# eink_controller.net
KiCad netlist of a schematic drawn in EAGLE
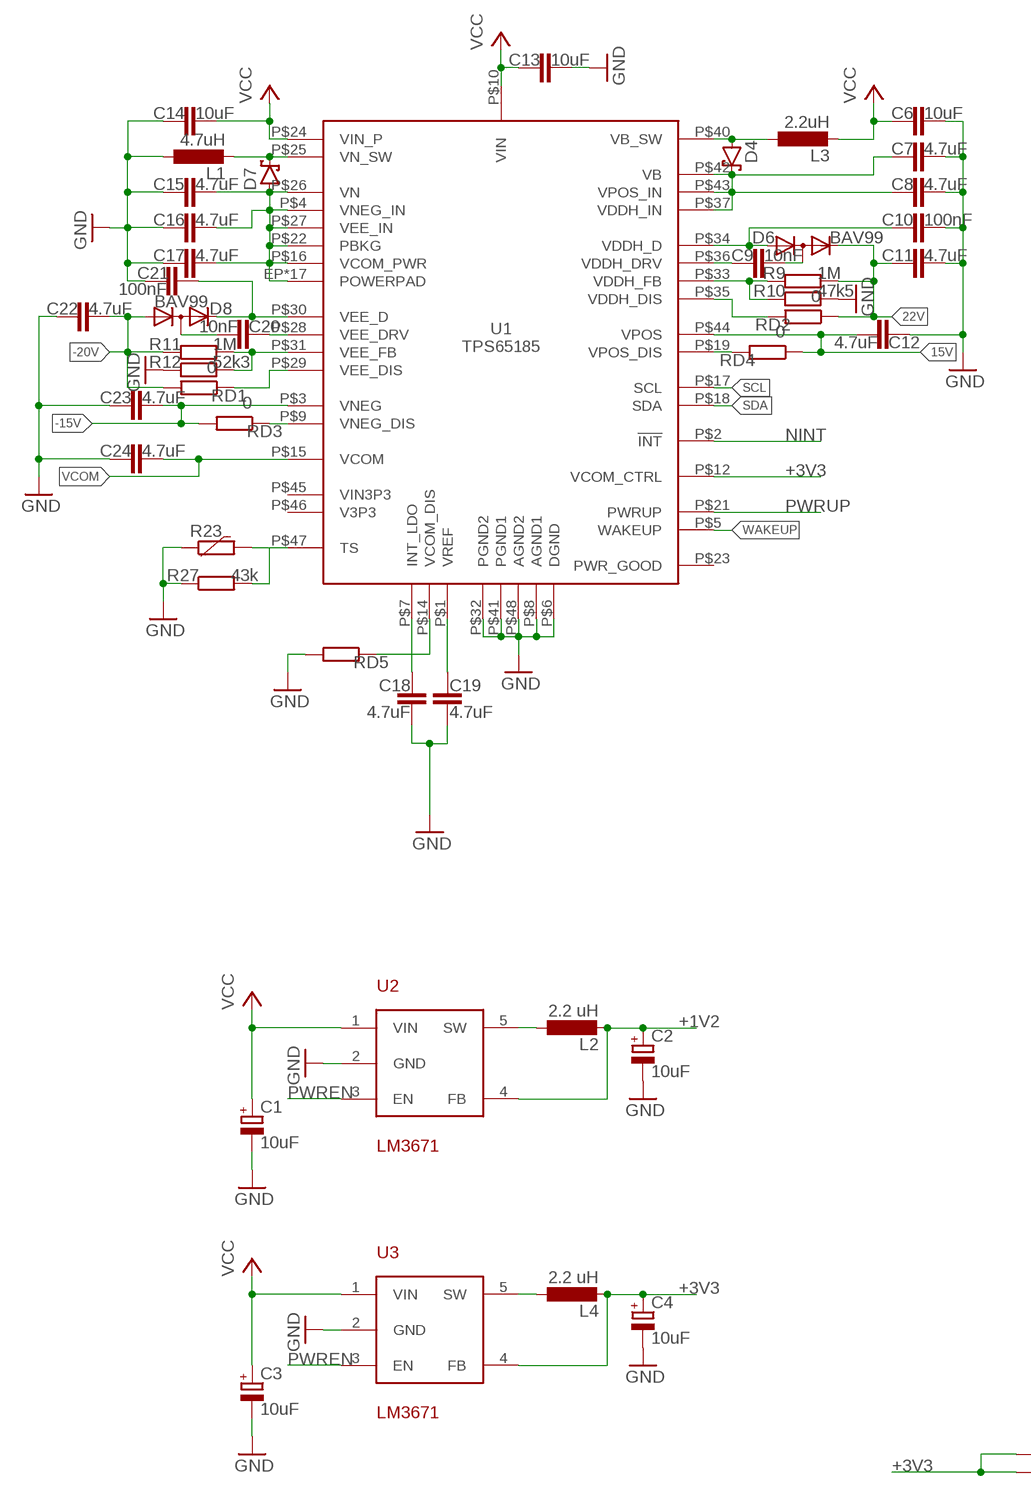
[diagram p0: schematic, sheet 1, part 1 of 2]
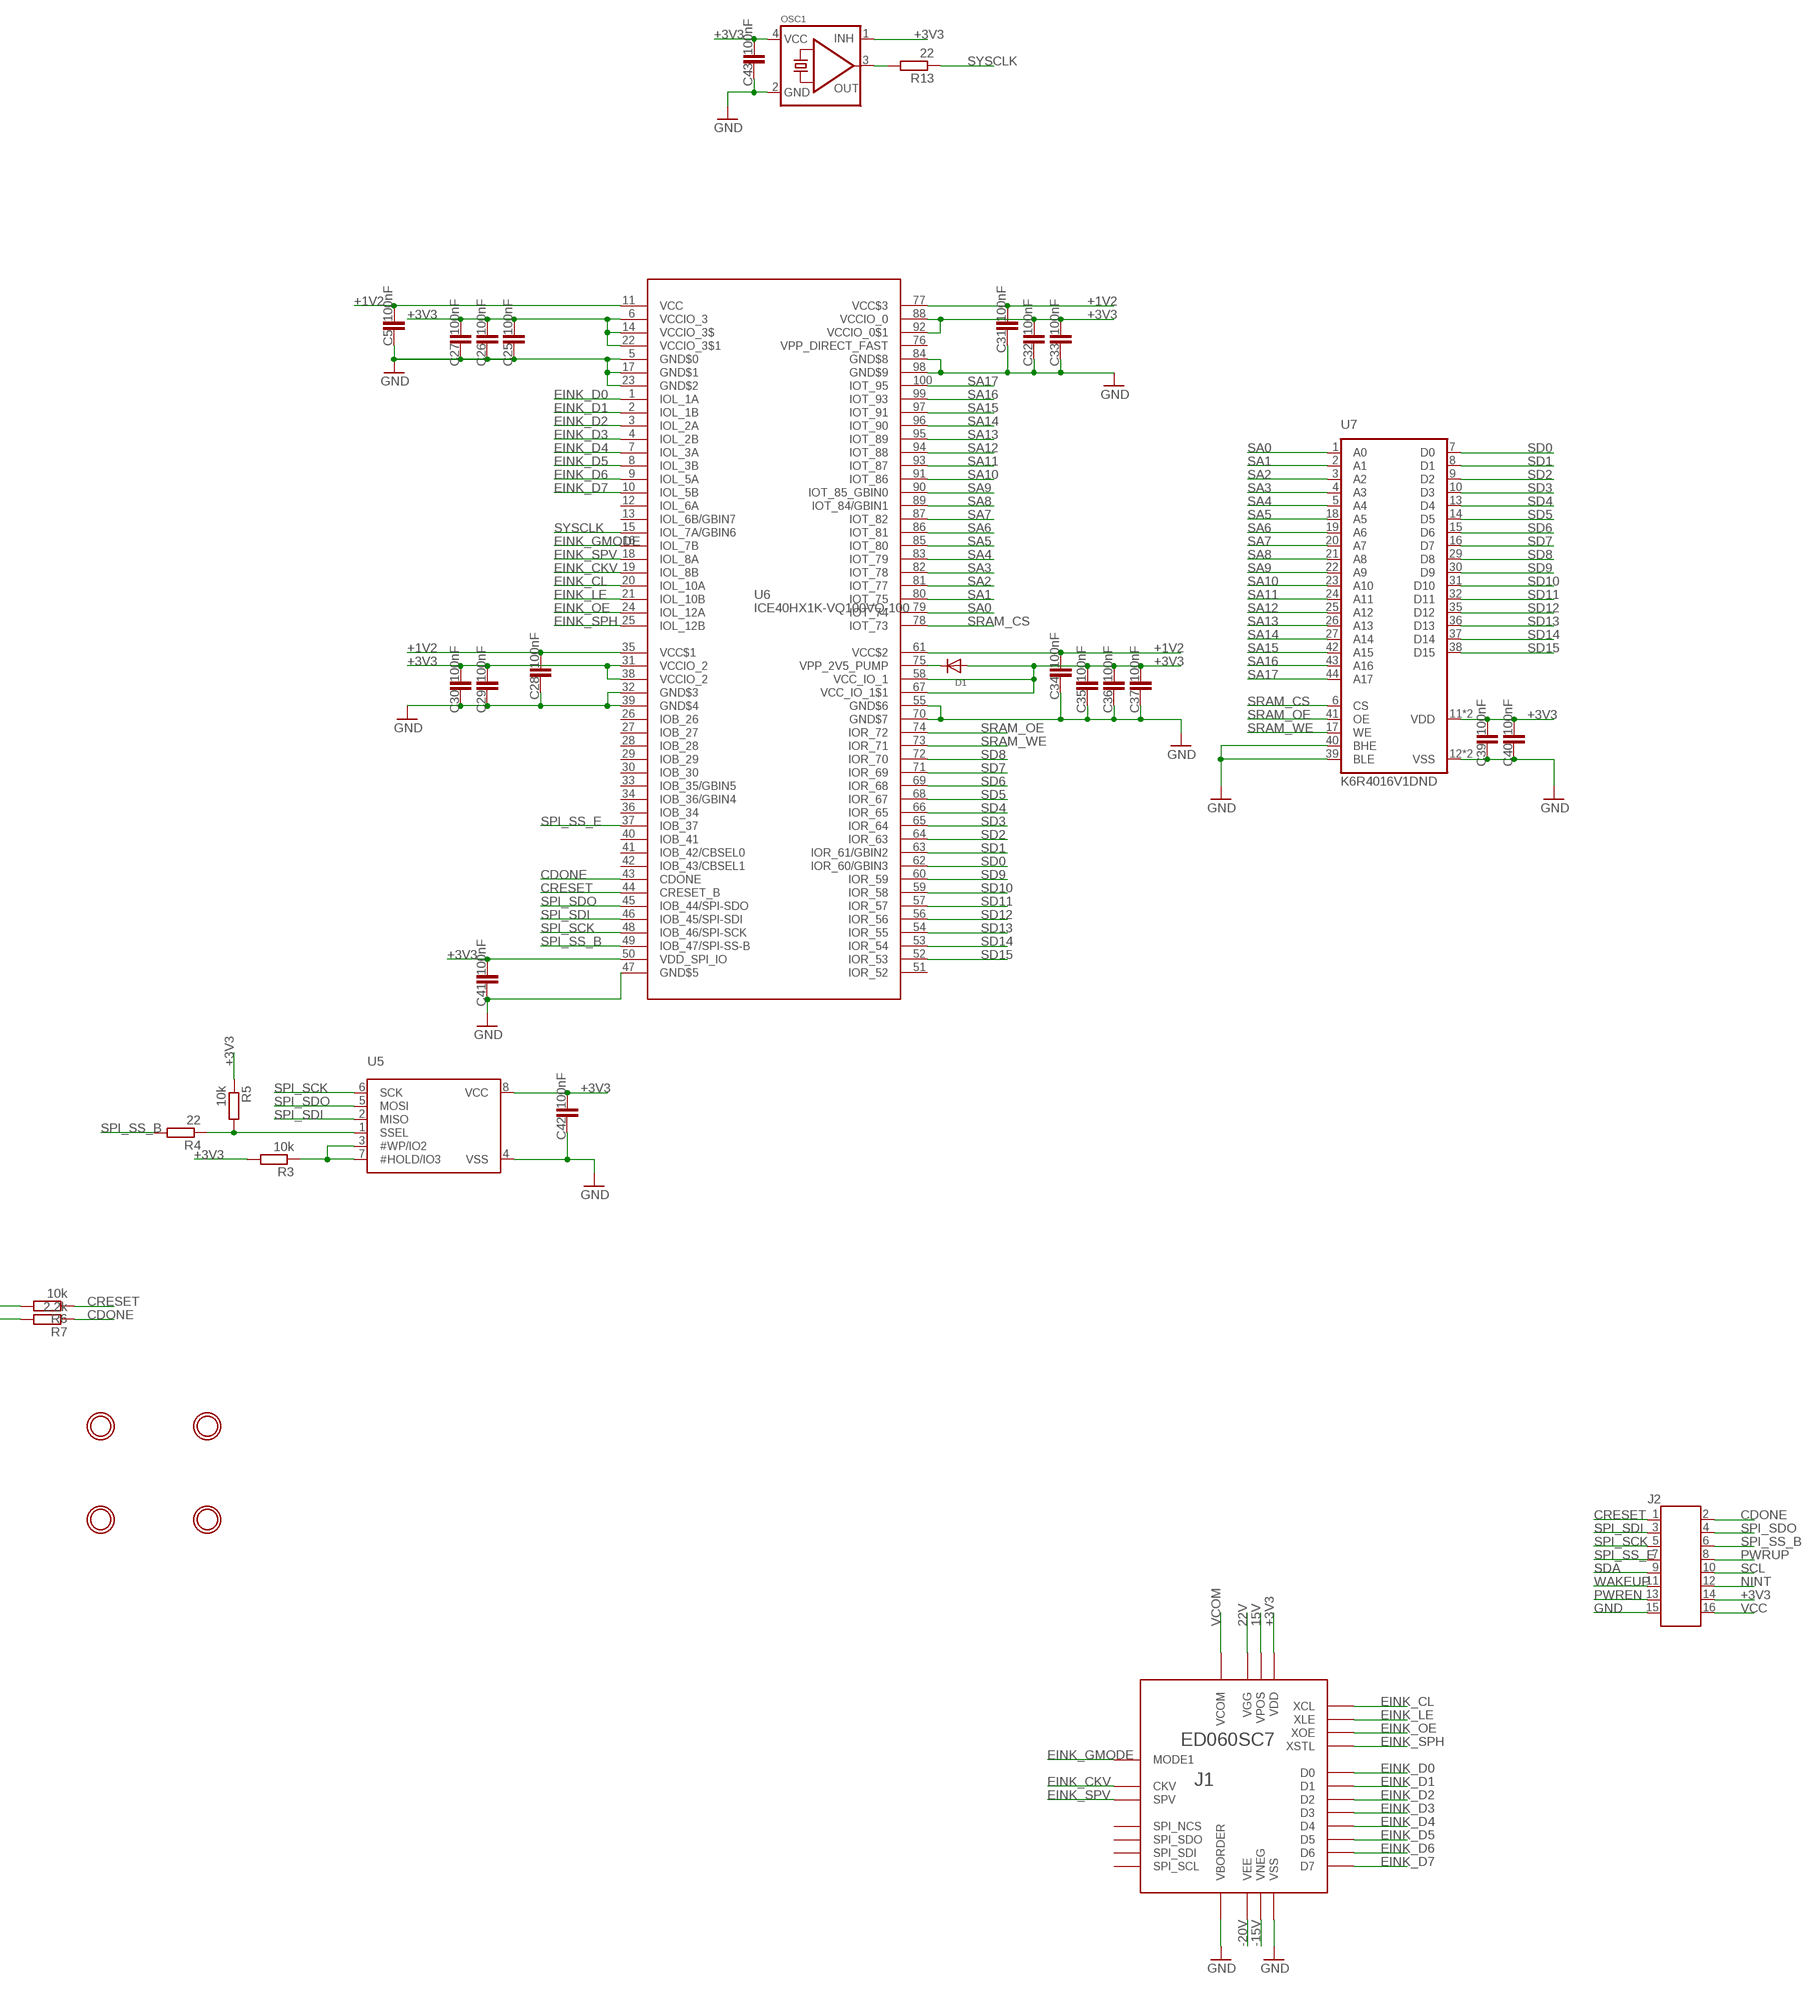
[diagram p1: schematic, sheet 1, part 2 of 2]

(export (version "E")
  (design (tool "Eeschema 10.0.6"))
  (components
    (comp (ref "C1")
      (value "10uF")
      (footprint "eagle-import:A_3216-18R")
      (libsource (lib "eagle-import") (part "CPOL-EUA/3216-18R"))
    )
    (comp (ref "C2")
      (value "10uF")
      (footprint "eagle-import:A_3216-18R")
      (libsource (lib "eagle-import") (part "CPOL-EUA/3216-18R"))
    )
    (comp (ref "C3")
      (value "10uF")
      (footprint "eagle-import:A_3216-18R")
      (libsource (lib "eagle-import") (part "CPOL-EUA/3216-18R"))
    )
    (comp (ref "C4")
      (value "10uF")
      (footprint "eagle-import:A_3216-18R")
      (libsource (lib "eagle-import") (part "CPOL-EUA/3216-18R"))
    )
    (comp (ref "C5")
      (value "100nF")
      (footprint "eagle-import:C0603K")
      (libsource (lib "eagle-import") (part "C-EUC0603K"))
    )
    (comp (ref "C6")
      (value "10uF")
      (footprint "eagle-import:C0805K")
      (libsource (lib "eagle-import") (part "C-EUC0805K"))
    )
    (comp (ref "C7")
      (value "4.7uF")
      (footprint "eagle-import:C0805K")
      (libsource (lib "eagle-import") (part "C-EUC0805K"))
    )
    (comp (ref "C8")
      (value "4.7uF")
      (footprint "eagle-import:C0805K")
      (libsource (lib "eagle-import") (part "C-EUC0805K"))
    )
    (comp (ref "C9")
      (value "10nF")
      (footprint "eagle-import:C0603K")
      (libsource (lib "eagle-import") (part "C-EUC0603K"))
    )
    (comp (ref "C10")
      (value "100nF")
      (footprint "eagle-import:C0603K")
      (libsource (lib "eagle-import") (part "C-EUC0603K"))
    )
    (comp (ref "C11")
      (value "4.7uF")
      (footprint "eagle-import:C0603K")
      (libsource (lib "eagle-import") (part "C-EUC0603K"))
    )
    (comp (ref "C12")
      (value "4.7uF")
      (footprint "eagle-import:C0805K")
      (libsource (lib "eagle-import") (part "C-EUC0805K"))
    )
    (comp (ref "C13")
      (value "10uF")
      (footprint "eagle-import:C0805K")
      (libsource (lib "eagle-import") (part "C-EUC0805K"))
    )
    (comp (ref "C14")
      (value "10uF")
      (footprint "eagle-import:C0805K")
      (libsource (lib "eagle-import") (part "C-EUC0805K"))
    )
    (comp (ref "C15")
      (value "4.7uF")
      (footprint "eagle-import:C0805K")
      (libsource (lib "eagle-import") (part "C-EUC0805K"))
    )
    (comp (ref "C16")
      (value "4.7uF")
      (footprint "eagle-import:C0805K")
      (libsource (lib "eagle-import") (part "C-EUC0805K"))
    )
    (comp (ref "C17")
      (value "4.7uF")
      (footprint "eagle-import:C0805K")
      (libsource (lib "eagle-import") (part "C-EUC0805K"))
    )
    (comp (ref "C18")
      (value "4.7uF")
      (footprint "eagle-import:C0805K")
      (libsource (lib "eagle-import") (part "C-EUC0805K"))
    )
    (comp (ref "C19")
      (value "4.7uF")
      (footprint "eagle-import:C0805K")
      (libsource (lib "eagle-import") (part "C-EUC0805K"))
    )
    (comp (ref "C20")
      (value "10nF")
      (footprint "eagle-import:C0603K")
      (libsource (lib "eagle-import") (part "C-EUC0603K"))
    )
    (comp (ref "C21")
      (value "100nF")
      (footprint "eagle-import:C0603K")
      (libsource (lib "eagle-import") (part "C-EUC0603K"))
    )
    (comp (ref "C22")
      (value "4.7uF")
      (footprint "eagle-import:C0603K")
      (libsource (lib "eagle-import") (part "C-EUC0603K"))
    )
    (comp (ref "C23")
      (value "4.7uF")
      (footprint "eagle-import:C0805K")
      (libsource (lib "eagle-import") (part "C-EUC0805K"))
    )
    (comp (ref "C24")
      (value "4.7uF")
      (footprint "eagle-import:C0805K")
      (libsource (lib "eagle-import") (part "C-EUC0805K"))
    )
    (comp (ref "C25")
      (value "100nF")
      (footprint "eagle-import:C0603K")
      (libsource (lib "eagle-import") (part "C-EUC0603K"))
    )
    (comp (ref "C26")
      (value "100nF")
      (footprint "eagle-import:C0603K")
      (libsource (lib "eagle-import") (part "C-EUC0603K"))
    )
    (comp (ref "C27")
      (value "100nF")
      (footprint "eagle-import:C0603K")
      (libsource (lib "eagle-import") (part "C-EUC0603K"))
    )
    (comp (ref "C28")
      (value "100nF")
      (footprint "eagle-import:C0603K")
      (libsource (lib "eagle-import") (part "C-EUC0603K"))
    )
    (comp (ref "C29")
      (value "100nF")
      (footprint "eagle-import:C0603K")
      (libsource (lib "eagle-import") (part "C-EUC0603K"))
    )
    (comp (ref "C30")
      (value "100nF")
      (footprint "eagle-import:C0603K")
      (libsource (lib "eagle-import") (part "C-EUC0603K"))
    )
    (comp (ref "C31")
      (value "100nF")
      (footprint "eagle-import:C0603K")
      (libsource (lib "eagle-import") (part "C-EUC0603K"))
    )
    (comp (ref "C32")
      (value "100nF")
      (footprint "eagle-import:C0603K")
      (libsource (lib "eagle-import") (part "C-EUC0603K"))
    )
    (comp (ref "C33")
      (value "100nF")
      (footprint "eagle-import:C0603K")
      (libsource (lib "eagle-import") (part "C-EUC0603K"))
    )
    (comp (ref "C34")
      (value "100nF")
      (footprint "eagle-import:C0603K")
      (libsource (lib "eagle-import") (part "C-EUC0603K"))
    )
    (comp (ref "C35")
      (value "100nF")
      (footprint "eagle-import:C0603K")
      (libsource (lib "eagle-import") (part "C-EUC0603K"))
    )
    (comp (ref "C36")
      (value "100nF")
      (footprint "eagle-import:C0603K")
      (libsource (lib "eagle-import") (part "C-EUC0603K"))
    )
    (comp (ref "C37")
      (value "100nF")
      (footprint "eagle-import:C0603K")
      (libsource (lib "eagle-import") (part "C-EUC0603K"))
    )
    (comp (ref "C39")
      (value "100nF")
      (footprint "eagle-import:C0603K")
      (libsource (lib "eagle-import") (part "C-EUC0603K"))
    )
    (comp (ref "C40")
      (value "100nF")
      (footprint "eagle-import:C0603K")
      (libsource (lib "eagle-import") (part "C-EUC0603K"))
    )
    (comp (ref "C41")
      (value "100nF")
      (footprint "eagle-import:C0603K")
      (libsource (lib "eagle-import") (part "C-EUC0603K"))
    )
    (comp (ref "C42")
      (value "100nF")
      (footprint "eagle-import:C0603K")
      (libsource (lib "eagle-import") (part "C-EUC0603K"))
    )
    (comp (ref "C43")
      (value "100nF")
      (footprint "eagle-import:C0603K")
      (libsource (lib "eagle-import") (part "C-EUC0603K"))
    )
    (comp (ref "D1")
      (value "DIODESOD-123")
      (footprint "eagle-import:SOD-123")
      (libsource (lib "eagle-import") (part "DIODESOD-123"))
    )
    (comp (ref "D4")
      (value "MBR130T3G")
      (footprint "eagle-import:SOD123")
      (libsource (lib "eagle-import") (part "MBR130T3G"))
    )
    (comp (ref "D6")
      (value "BAV99")
      (footprint "eagle-import:SOT23")
      (libsource (lib "eagle-import") (part "BAV199"))
    )
    (comp (ref "D7")
      (value "MBR130T3G")
      (footprint "eagle-import:SOD123")
      (libsource (lib "eagle-import") (part "MBR130T3G"))
    )
    (comp (ref "D8")
      (value "BAV99")
      (footprint "eagle-import:SOT23")
      (libsource (lib "eagle-import") (part "BAV199"))
    )
    (comp (ref "J1")
      (value "ED060SC7")
      (footprint "eagle-import:AXT334124")
      (libsource (lib "eagle-import") (part "ED060SC7"))
    )
    (comp (ref "J2")
      (value "610116249221")
      (footprint "eagle-import:610116249221")
      (libsource (lib "eagle-import") (part "610116249221"))
    )
    (comp (ref "L1")
      (value "4.7uH")
      (footprint "eagle-import:L2825P")
      (libsource (lib "eagle-import") (part "L-EUL2825P"))
    )
    (comp (ref "L2")
      (value "2.2 uH")
      (footprint "eagle-import:L2825P")
      (libsource (lib "eagle-import") (part "L-EUL2825P"))
    )
    (comp (ref "L3")
      (value "2.2uH")
      (footprint "eagle-import:L2825P")
      (libsource (lib "eagle-import") (part "L-EUL2825P"))
    )
    (comp (ref "L4")
      (value "2.2 uH")
      (footprint "eagle-import:L2825P")
      (libsource (lib "eagle-import") (part "L-EUL2825P"))
    )
    (comp (ref "OSC1")
      (value "OSCILLATOR")
      (footprint "eagle-import:OSC_7X5MM")
      (libsource (lib "eagle-import") (part "OSCILLATOR"))
    )
    (comp (ref "R3")
      (value "10k")
      (footprint "eagle-import:R0603")
      (libsource (lib "eagle-import") (part "R-EU_R0603"))
    )
    (comp (ref "R4")
      (value "22")
      (footprint "eagle-import:R0603")
      (libsource (lib "eagle-import") (part "R-EU_R0603"))
    )
    (comp (ref "R5")
      (value "10k")
      (footprint "eagle-import:R0603")
      (libsource (lib "eagle-import") (part "R-EU_R0603"))
    )
    (comp (ref "R6")
      (value "10k")
      (footprint "eagle-import:R0603")
      (libsource (lib "eagle-import") (part "R-EU_R0603"))
    )
    (comp (ref "R7")
      (value "2.2k")
      (footprint "eagle-import:R0603")
      (libsource (lib "eagle-import") (part "R-EU_R0603"))
    )
    (comp (ref "R9")
      (value "1M")
      (footprint "eagle-import:R0603")
      (libsource (lib "eagle-import") (part "R-EU_R0603"))
    )
    (comp (ref "R10")
      (value "47k5")
      (footprint "eagle-import:R0603")
      (libsource (lib "eagle-import") (part "R-EU_R0603"))
    )
    (comp (ref "R11")
      (value "1M")
      (footprint "eagle-import:R0603")
      (libsource (lib "eagle-import") (part "R-EU_R0603"))
    )
    (comp (ref "R12")
      (value "52k3")
      (footprint "eagle-import:R0603")
      (libsource (lib "eagle-import") (part "R-EU_R0603"))
    )
    (comp (ref "R13")
      (value "22")
      (footprint "eagle-import:R0603")
      (libsource (lib "eagle-import") (part "R-EU_R0603"))
    )
    (comp (ref "R23")
      (value "R-EU_R0603")
      (footprint "eagle-import:R0603")
      (libsource (lib "eagle-import") (part "R-EU_R0603"))
    )
    (comp (ref "R27")
      (value "43k")
      (footprint "eagle-import:R0603")
      (libsource (lib "eagle-import") (part "R-EU_R0603"))
    )
    (comp (ref "RD1")
      (value "0")
      (footprint "eagle-import:R0603")
      (libsource (lib "eagle-import") (part "R-EU_R0603"))
    )
    (comp (ref "RD2")
      (value "0")
      (footprint "eagle-import:R0603")
      (libsource (lib "eagle-import") (part "R-EU_R0603"))
    )
    (comp (ref "RD3")
      (value "0")
      (footprint "eagle-import:R0603")
      (libsource (lib "eagle-import") (part "R-EU_R0603"))
    )
    (comp (ref "RD4")
      (value "0")
      (footprint "eagle-import:R0603")
      (libsource (lib "eagle-import") (part "R-EU_R0603"))
    )
    (comp (ref "RD5")
      (value "R-EU_R0603")
      (footprint "eagle-import:R0603")
      (libsource (lib "eagle-import") (part "R-EU_R0603"))
    )
    (comp (ref "U$1")
      (value "MOUNTINGHOLE2.0")
      (footprint "eagle-import:MOUNTINGHOLE_2.0_PLATED")
      (libsource (lib "eagle-import") (part "MOUNTINGHOLE2.0"))
    )
    (comp (ref "U$2")
      (value "MOUNTINGHOLE2.0")
      (footprint "eagle-import:MOUNTINGHOLE_2.0_PLATED")
      (libsource (lib "eagle-import") (part "MOUNTINGHOLE2.0"))
    )
    (comp (ref "U$3")
      (value "MOUNTINGHOLE2.0")
      (footprint "eagle-import:MOUNTINGHOLE_2.0_PLATED")
      (libsource (lib "eagle-import") (part "MOUNTINGHOLE2.0"))
    )
    (comp (ref "U$4")
      (value "MOUNTINGHOLE2.0")
      (footprint "eagle-import:MOUNTINGHOLE_2.0_PLATED")
      (libsource (lib "eagle-import") (part "MOUNTINGHOLE2.0"))
    )
    (comp (ref "U1")
      (value "TPS65185")
      (footprint "eagle-import:VQFN48")
      (libsource (lib "eagle-import") (part "TPS65185"))
    )
    (comp (ref "U2")
      (value "LM3671")
      (footprint "eagle-import:SOT23-5")
      (libsource (lib "eagle-import") (part "LM3671"))
    )
    (comp (ref "U3")
      (value "LM3671")
      (footprint "eagle-import:SOT23-5")
      (libsource (lib "eagle-import") (part "LM3671"))
    )
    (comp (ref "U5")
      (value "SPIFLASH_SOIC8208MIL")
      (footprint "eagle-import:SOIC8_208MIL")
      (libsource (lib "eagle-import") (part "SPIFLASH_SOIC8208MIL"))
    )
    (comp (ref "U6")
      (value "ICE40HX1K-VQ100VQ-100")
      (footprint "eagle-import:TQFP100")
      (libsource (lib "eagle-import") (part "ICE40HX1K-VQ100VQ-100"))
    )
    (comp (ref "U7")
      (value "K6R4016V1DND")
      (footprint "eagle-import:TSOP44-II")
      (libsource (lib "eagle-import") (part "K6R4016V1DND"))
    )
  )
  (nets
    (net (code "1") (name "-15V") (class "Default")
      (node (ref "C23") (pin "2") (pinfunction "2_2") (pintype "passive"))
      (node (ref "J1") (pin "P$1") (pinfunction "VNEG_P$1") (pintype "bidirectional"))
      (node (ref "J1") (pin "P$3") (pinfunction "VNEG_P$3") (pintype "bidirectional"))
      (node (ref "RD3") (pin "2") (pinfunction "2_2") (pintype "passive"))
      (node (ref "U1") (pin "P$3") (pinfunction "VNEG_P$3") (pintype "bidirectional"))
    )
    (net (code "2") (name "-20V") (class "Default")
      (node (ref "C22") (pin "2") (pinfunction "2_2") (pintype "passive"))
      (node (ref "D8") (pin "1") (pinfunction "A_1") (pintype "passive"))
      (node (ref "J1") (pin "P$27") (pinfunction "VEE_P$27") (pintype "bidirectional"))
      (node (ref "J1") (pin "P$29") (pinfunction "VEE_P$29") (pintype "bidirectional"))
      (node (ref "R11") (pin "1") (pinfunction "1_1") (pintype "passive"))
      (node (ref "RD1") (pin "2") (pinfunction "2_2") (pintype "passive"))
    )
    (net (code "3") (name "/+1V2") (class "Default")
      (node (ref "C2") (pin "+") (pinfunction "+_+") (pintype "passive"))
      (node (ref "C28") (pin "2") (pinfunction "2_2") (pintype "passive"))
      (node (ref "C31") (pin "2") (pinfunction "2_2") (pintype "passive"))
      (node (ref "C34") (pin "2") (pinfunction "2_2") (pintype "passive"))
      (node (ref "C5") (pin "2") (pinfunction "2_2") (pintype "passive"))
      (node (ref "L2") (pin "2") (pinfunction "2_2") (pintype "passive"))
      (node (ref "U2") (pin "4") (pinfunction "FB_4") (pintype "bidirectional"))
      (node (ref "U6") (pin "11") (pinfunction "VCC_11") (pintype "power_in"))
      (node (ref "U6") (pin "35") (pinfunction "VCC$1_35") (pintype "bidirectional"))
      (node (ref "U6") (pin "61") (pinfunction "VCC$2_61") (pintype "bidirectional"))
      (node (ref "U6") (pin "77") (pinfunction "VCC$3_77") (pintype "bidirectional"))
    )
    (net (code "4") (name "/+3V3") (class "Default")
      (node (ref "C25") (pin "2") (pinfunction "2_2") (pintype "passive"))
      (node (ref "C26") (pin "2") (pinfunction "2_2") (pintype "passive"))
      (node (ref "C27") (pin "2") (pinfunction "2_2") (pintype "passive"))
      (node (ref "C29") (pin "2") (pinfunction "2_2") (pintype "passive"))
      (node (ref "C30") (pin "2") (pinfunction "2_2") (pintype "passive"))
      (node (ref "C32") (pin "2") (pinfunction "2_2") (pintype "passive"))
      (node (ref "C33") (pin "2") (pinfunction "2_2") (pintype "passive"))
      (node (ref "C35") (pin "2") (pinfunction "2_2") (pintype "passive"))
      (node (ref "C36") (pin "2") (pinfunction "2_2") (pintype "passive"))
      (node (ref "C37") (pin "2") (pinfunction "2_2") (pintype "passive"))
      (node (ref "C39") (pin "2") (pinfunction "2_2") (pintype "passive"))
      (node (ref "C4") (pin "+") (pinfunction "+_+") (pintype "passive"))
      (node (ref "C40") (pin "2") (pinfunction "2_2") (pintype "passive"))
      (node (ref "C41") (pin "2") (pinfunction "2_2") (pintype "passive"))
      (node (ref "C42") (pin "2") (pinfunction "2_2") (pintype "passive"))
      (node (ref "C43") (pin "2") (pinfunction "2_2") (pintype "passive"))
      (node (ref "D1") (pin "A") (pinfunction "A_A") (pintype "passive"))
      (node (ref "J1") (pin "P$5") (pinfunction "VDD_P$5") (pintype "bidirectional"))
      (node (ref "J1") (pin "P$7") (pinfunction "VDD_P$7") (pintype "bidirectional"))
      (node (ref "J2") (pin "14") (pinfunction "14_14") (pintype "passive"))
      (node (ref "L4") (pin "2") (pinfunction "2_2") (pintype "passive"))
      (node (ref "OSC1") (pin "1") (pinfunction "INH_1") (pintype "bidirectional"))
      (node (ref "OSC1") (pin "4") (pinfunction "VCC_4") (pintype "power_in"))
      (node (ref "R3") (pin "2") (pinfunction "2_2") (pintype "passive"))
      (node (ref "R5") (pin "1") (pinfunction "1_1") (pintype "passive"))
      (node (ref "R6") (pin "2") (pinfunction "2_2") (pintype "passive"))
      (node (ref "R7") (pin "2") (pinfunction "2_2") (pintype "passive"))
      (node (ref "U1") (pin "P$12") (pinfunction "VCOM_CTRL_P$12") (pintype "bidirectional"))
      (node (ref "U3") (pin "4") (pinfunction "FB_4") (pintype "bidirectional"))
      (node (ref "U5") (pin "8") (pinfunction "VCC_8") (pintype "bidirectional"))
      (node (ref "U6") (pin "14") (pinfunction "VCCIO_3$_14") (pintype "power_in"))
      (node (ref "U6") (pin "22") (pinfunction "VCCIO_3$1_22") (pintype "power_in"))
      (node (ref "U6") (pin "31") (pinfunction "VCCIO_2_31") (pintype "power_in"))
      (node (ref "U6") (pin "38") (pinfunction "VCCIO_2_38") (pintype "power_in"))
      (node (ref "U6") (pin "50") (pinfunction "VDD_SPI_IO_50") (pintype "power_in"))
      (node (ref "U6") (pin "58") (pinfunction "VCC_IO_1_58") (pintype "power_in"))
      (node (ref "U6") (pin "6") (pinfunction "VCCIO_3_6") (pintype "power_in"))
      (node (ref "U6") (pin "67") (pinfunction "VCC_IO_1$1_67") (pintype "power_in"))
      (node (ref "U6") (pin "88") (pinfunction "VCCIO_0_88") (pintype "input"))
      (node (ref "U6") (pin "92") (pinfunction "VCCIO_0$1_92") (pintype "power_in"))
      (node (ref "U7") (pin "11") (pinfunction "VDD_11") (pintype "bidirectional"))
      (node (ref "U7") (pin "33") (pinfunction "VDD_33") (pintype "bidirectional"))
    )
    (net (code "5") (name "/CDONE") (class "Default")
      (node (ref "J2") (pin "2") (pinfunction "2_2") (pintype "passive"))
      (node (ref "R7") (pin "1") (pinfunction "1_1") (pintype "passive"))
      (node (ref "U6") (pin "43") (pinfunction "CDONE_43") (pintype "output"))
    )
    (net (code "6") (name "/CRESET") (class "Default")
      (node (ref "J2") (pin "1") (pinfunction "1_1") (pintype "passive"))
      (node (ref "R6") (pin "1") (pinfunction "1_1") (pintype "passive"))
      (node (ref "U6") (pin "44") (pinfunction "CRESET_B_44") (pintype "bidirectional"))
    )
    (net (code "7") (name "/EINK_CKV") (class "Default")
      (node (ref "J1") (pin "P$28") (pinfunction "CKV_P$28") (pintype "bidirectional"))
      (node (ref "U6") (pin "19") (pinfunction "IOL_8B_19") (pintype "bidirectional"))
    )
    (net (code "8") (name "/EINK_CL") (class "Default")
      (node (ref "J1") (pin "P$9") (pinfunction "XCL_P$9") (pintype "bidirectional"))
      (node (ref "U6") (pin "20") (pinfunction "IOL_10A_20") (pintype "bidirectional"))
    )
    (net (code "9") (name "/EINK_D0") (class "Default")
      (node (ref "J1") (pin "P$13") (pinfunction "D0_P$13") (pintype "bidirectional"))
      (node (ref "U6") (pin "1") (pinfunction "IOL_1A_1") (pintype "bidirectional"))
    )
    (net (code "10") (name "/EINK_D1") (class "Default")
      (node (ref "J1") (pin "P$14") (pinfunction "D1_P$14") (pintype "bidirectional"))
      (node (ref "U6") (pin "2") (pinfunction "IOL_1B_2") (pintype "bidirectional"))
    )
    (net (code "11") (name "/EINK_D2") (class "Default")
      (node (ref "J1") (pin "P$15") (pinfunction "D2_P$15") (pintype "bidirectional"))
      (node (ref "U6") (pin "3") (pinfunction "IOL_2A_3") (pintype "bidirectional"))
    )
    (net (code "12") (name "/EINK_D3") (class "Default")
      (node (ref "J1") (pin "P$16") (pinfunction "D3_P$16") (pintype "bidirectional"))
      (node (ref "U6") (pin "4") (pinfunction "IOL_2B_4") (pintype "bidirectional"))
    )
    (net (code "13") (name "/EINK_D4") (class "Default")
      (node (ref "J1") (pin "P$17") (pinfunction "D4_P$17") (pintype "bidirectional"))
      (node (ref "U6") (pin "7") (pinfunction "IOL_3A_7") (pintype "bidirectional"))
    )
    (net (code "14") (name "/EINK_D5") (class "Default")
      (node (ref "J1") (pin "P$18") (pinfunction "D5_P$18") (pintype "bidirectional"))
      (node (ref "U6") (pin "8") (pinfunction "IOL_3B_8") (pintype "bidirectional"))
    )
    (net (code "15") (name "/EINK_D6") (class "Default")
      (node (ref "J1") (pin "P$19") (pinfunction "D6_P$19") (pintype "bidirectional"))
      (node (ref "U6") (pin "9") (pinfunction "IOL_5A_9") (pintype "bidirectional"))
    )
    (net (code "16") (name "/EINK_D7") (class "Default")
      (node (ref "J1") (pin "P$20") (pinfunction "D7_P$20") (pintype "bidirectional"))
      (node (ref "U6") (pin "10") (pinfunction "IOL_5B_10") (pintype "bidirectional"))
    )
    (net (code "17") (name "/EINK_GMODE") (class "Default")
      (node (ref "J1") (pin "P$26") (pinfunction "MODE1_P$26") (pintype "bidirectional"))
      (node (ref "U6") (pin "16") (pinfunction "IOL_7B_16") (pintype "bidirectional"))
    )
    (net (code "18") (name "/EINK_LE") (class "Default")
      (node (ref "J1") (pin "P$10") (pinfunction "XLE_P$10") (pintype "bidirectional"))
      (node (ref "U6") (pin "21") (pinfunction "IOL_10B_21") (pintype "bidirectional"))
    )
    (net (code "19") (name "/EINK_OE") (class "Default")
      (node (ref "J1") (pin "P$11") (pinfunction "XOE_P$11") (pintype "bidirectional"))
      (node (ref "U6") (pin "24") (pinfunction "IOL_12A_24") (pintype "bidirectional"))
    )
    (net (code "20") (name "/EINK_SPH") (class "Default")
      (node (ref "J1") (pin "P$12") (pinfunction "XSTL_P$12") (pintype "bidirectional"))
      (node (ref "U6") (pin "25") (pinfunction "IOL_12B_25") (pintype "bidirectional"))
    )
    (net (code "21") (name "/EINK_SPV") (class "Default")
      (node (ref "J1") (pin "P$30") (pinfunction "SPV_P$30") (pintype "bidirectional"))
      (node (ref "U6") (pin "18") (pinfunction "IOL_8A_18") (pintype "bidirectional"))
    )
    (net (code "22") (name "/NINT") (class "Default")
      (node (ref "J2") (pin "12") (pinfunction "12_12") (pintype "passive"))
      (node (ref "U1") (pin "P$2") (pinfunction "~{INT}_P$2") (pintype "bidirectional"))
    )
    (net (code "23") (name "/PWREN") (class "Default")
      (node (ref "J2") (pin "13") (pinfunction "13_13") (pintype "passive"))
      (node (ref "U2") (pin "3") (pinfunction "EN_3") (pintype "bidirectional"))
      (node (ref "U3") (pin "3") (pinfunction "EN_3") (pintype "bidirectional"))
    )
    (net (code "24") (name "/PWRUP") (class "Default")
      (node (ref "J2") (pin "8") (pinfunction "8_8") (pintype "passive"))
      (node (ref "U1") (pin "P$21") (pinfunction "PWRUP_P$21") (pintype "bidirectional"))
    )
    (net (code "25") (name "/SA0") (class "Default")
      (node (ref "U6") (pin "79") (pinfunction "IOT_74_79") (pintype "bidirectional"))
      (node (ref "U7") (pin "1") (pinfunction "A0_1") (pintype "input"))
    )
    (net (code "26") (name "/SA1") (class "Default")
      (node (ref "U6") (pin "80") (pinfunction "IOT_75_80") (pintype "bidirectional"))
      (node (ref "U7") (pin "2") (pinfunction "A1_2") (pintype "input"))
    )
    (net (code "27") (name "/SA2") (class "Default")
      (node (ref "U6") (pin "81") (pinfunction "IOT_77_81") (pintype "bidirectional"))
      (node (ref "U7") (pin "3") (pinfunction "A2_3") (pintype "input"))
    )
    (net (code "28") (name "/SA3") (class "Default")
      (node (ref "U6") (pin "82") (pinfunction "IOT_78_82") (pintype "power_in"))
      (node (ref "U7") (pin "4") (pinfunction "A3_4") (pintype "input"))
    )
    (net (code "29") (name "/SA4") (class "Default")
      (node (ref "U6") (pin "83") (pinfunction "IOT_79_83") (pintype "bidirectional"))
      (node (ref "U7") (pin "5") (pinfunction "A4_5") (pintype "input"))
    )
    (net (code "30") (name "/SA5") (class "Default")
      (node (ref "U6") (pin "85") (pinfunction "IOT_80_85") (pintype "bidirectional"))
      (node (ref "U7") (pin "18") (pinfunction "A5_18") (pintype "input"))
    )
    (net (code "31") (name "/SA6") (class "Default")
      (node (ref "U6") (pin "86") (pinfunction "IOT_81_86") (pintype "bidirectional"))
      (node (ref "U7") (pin "19") (pinfunction "A6_19") (pintype "input"))
    )
    (net (code "32") (name "/SA7") (class "Default")
      (node (ref "U6") (pin "87") (pinfunction "IOT_82_87") (pintype "bidirectional"))
      (node (ref "U7") (pin "20") (pinfunction "A7_20") (pintype "input"))
    )
    (net (code "33") (name "/SA8") (class "Default")
      (node (ref "U6") (pin "89") (pinfunction "IOT_84/GBIN1_89") (pintype "output"))
      (node (ref "U7") (pin "21") (pinfunction "A8_21") (pintype "input"))
    )
    (net (code "34") (name "/SA9") (class "Default")
      (node (ref "U6") (pin "90") (pinfunction "IOT_85_GBIN0_90") (pintype "bidirectional"))
      (node (ref "U7") (pin "22") (pinfunction "A9_22") (pintype "input"))
    )
    (net (code "35") (name "/SA10") (class "Default")
      (node (ref "U6") (pin "91") (pinfunction "IOT_86_91") (pintype "bidirectional"))
      (node (ref "U7") (pin "23") (pinfunction "A10_23") (pintype "input"))
    )
    (net (code "36") (name "/SA11") (class "Default")
      (node (ref "U6") (pin "93") (pinfunction "IOT_87_93") (pintype "bidirectional"))
      (node (ref "U7") (pin "24") (pinfunction "A11_24") (pintype "input"))
    )
    (net (code "37") (name "/SA12") (class "Default")
      (node (ref "U6") (pin "94") (pinfunction "IOT_88_94") (pintype "bidirectional"))
      (node (ref "U7") (pin "25") (pinfunction "A12_25") (pintype "input"))
    )
    (net (code "38") (name "/SA13") (class "Default")
      (node (ref "U6") (pin "95") (pinfunction "IOT_89_95") (pintype "bidirectional"))
      (node (ref "U7") (pin "26") (pinfunction "A13_26") (pintype "input"))
    )
    (net (code "39") (name "/SA14") (class "Default")
      (node (ref "U6") (pin "96") (pinfunction "IOT_90_96") (pintype "bidirectional"))
      (node (ref "U7") (pin "27") (pinfunction "A14_27") (pintype "input"))
    )
    (net (code "40") (name "/SA15") (class "Default")
      (node (ref "U6") (pin "97") (pinfunction "IOT_91_97") (pintype "bidirectional"))
      (node (ref "U7") (pin "42") (pinfunction "A15_42") (pintype "input"))
    )
    (net (code "41") (name "/SA16") (class "Default")
      (node (ref "U6") (pin "99") (pinfunction "IOT_93_99") (pintype "bidirectional"))
      (node (ref "U7") (pin "43") (pinfunction "A16_43") (pintype "input"))
    )
    (net (code "42") (name "/SA17") (class "Default")
      (node (ref "U6") (pin "100") (pinfunction "IOT_95_100") (pintype "bidirectional"))
      (node (ref "U7") (pin "44") (pinfunction "A17_44") (pintype "bidirectional"))
    )
    (net (code "43") (name "/SD0") (class "Default")
      (node (ref "U6") (pin "62") (pinfunction "IOR_60/GBIN3_62") (pintype "bidirectional"))
      (node (ref "U7") (pin "7") (pinfunction "D0_7") (pintype "tri_state"))
    )
    (net (code "44") (name "/SD1") (class "Default")
      (node (ref "U6") (pin "63") (pinfunction "IOR_61/GBIN2_63") (pintype "bidirectional"))
      (node (ref "U7") (pin "8") (pinfunction "D1_8") (pintype "tri_state"))
    )
    (net (code "45") (name "/SD2") (class "Default")
      (node (ref "U6") (pin "64") (pinfunction "IOR_63_64") (pintype "bidirectional"))
      (node (ref "U7") (pin "9") (pinfunction "D2_9") (pintype "tri_state"))
    )
    (net (code "46") (name "/SD3") (class "Default")
      (node (ref "U6") (pin "65") (pinfunction "IOR_64_65") (pintype "bidirectional"))
      (node (ref "U7") (pin "10") (pinfunction "D3_10") (pintype "tri_state"))
    )
    (net (code "47") (name "/SD4") (class "Default")
      (node (ref "U6") (pin "66") (pinfunction "IOR_65_66") (pintype "bidirectional"))
      (node (ref "U7") (pin "13") (pinfunction "D4_13") (pintype "tri_state"))
    )
    (net (code "48") (name "/SD5") (class "Default")
      (node (ref "U6") (pin "68") (pinfunction "IOR_67_68") (pintype "bidirectional"))
      (node (ref "U7") (pin "14") (pinfunction "D5_14") (pintype "tri_state"))
    )
    (net (code "49") (name "/SD6") (class "Default")
      (node (ref "U6") (pin "69") (pinfunction "IOR_68_69") (pintype "bidirectional"))
      (node (ref "U7") (pin "15") (pinfunction "D6_15") (pintype "tri_state"))
    )
    (net (code "50") (name "/SD7") (class "Default")
      (node (ref "U6") (pin "71") (pinfunction "IOR_69_71") (pintype "bidirectional"))
      (node (ref "U7") (pin "16") (pinfunction "D7_16") (pintype "tri_state"))
    )
    (net (code "51") (name "/SD8") (class "Default")
      (node (ref "U6") (pin "72") (pinfunction "IOR_70_72") (pintype "bidirectional"))
      (node (ref "U7") (pin "29") (pinfunction "D8_29") (pintype "tri_state"))
    )
    (net (code "52") (name "/SD9") (class "Default")
      (node (ref "U6") (pin "60") (pinfunction "IOR_59_60") (pintype "bidirectional"))
      (node (ref "U7") (pin "30") (pinfunction "D9_30") (pintype "tri_state"))
    )
    (net (code "53") (name "/SD10") (class "Default")
      (node (ref "U6") (pin "59") (pinfunction "IOR_58_59") (pintype "bidirectional"))
      (node (ref "U7") (pin "31") (pinfunction "D10_31") (pintype "tri_state"))
    )
    (net (code "54") (name "/SD11") (class "Default")
      (node (ref "U6") (pin "57") (pinfunction "IOR_57_57") (pintype "bidirectional"))
      (node (ref "U7") (pin "32") (pinfunction "D11_32") (pintype "tri_state"))
    )
    (net (code "55") (name "/SD12") (class "Default")
      (node (ref "U6") (pin "56") (pinfunction "IOR_56_56") (pintype "bidirectional"))
      (node (ref "U7") (pin "35") (pinfunction "D12_35") (pintype "tri_state"))
    )
    (net (code "56") (name "/SD13") (class "Default")
      (node (ref "U6") (pin "54") (pinfunction "IOR_55_54") (pintype "bidirectional"))
      (node (ref "U7") (pin "36") (pinfunction "D13_36") (pintype "tri_state"))
    )
    (net (code "57") (name "/SD14") (class "Default")
      (node (ref "U6") (pin "53") (pinfunction "IOR_54_53") (pintype "bidirectional"))
      (node (ref "U7") (pin "37") (pinfunction "D14_37") (pintype "tri_state"))
    )
    (net (code "58") (name "/SD15") (class "Default")
      (node (ref "U6") (pin "52") (pinfunction "IOR_53_52") (pintype "bidirectional"))
      (node (ref "U7") (pin "38") (pinfunction "D15_38") (pintype "tri_state"))
    )
    (net (code "59") (name "/SPI_SCK") (class "Default")
      (node (ref "J2") (pin "5") (pinfunction "5_5") (pintype "passive"))
      (node (ref "U5") (pin "6") (pinfunction "SCK_6") (pintype "bidirectional"))
      (node (ref "U6") (pin "48") (pinfunction "IOB_46/SPI-SCK_48") (pintype "bidirectional"))
    )
    (net (code "60") (name "/SPI_SDI") (class "Default")
      (node (ref "J2") (pin "3") (pinfunction "3_3") (pintype "passive"))
      (node (ref "U5") (pin "2") (pinfunction "MISO_2") (pintype "bidirectional"))
      (node (ref "U6") (pin "46") (pinfunction "IOB_45/SPI-SDI_46") (pintype "bidirectional"))
    )
    (net (code "61") (name "/SPI_SDO") (class "Default")
      (node (ref "J2") (pin "4") (pinfunction "4_4") (pintype "passive"))
      (node (ref "U5") (pin "5") (pinfunction "MOSI_5") (pintype "bidirectional"))
      (node (ref "U6") (pin "45") (pinfunction "IOB_44/SPI-SDO_45") (pintype "bidirectional"))
    )
    (net (code "62") (name "/SPI_SS_B") (class "Default")
      (node (ref "J2") (pin "6") (pinfunction "6_6") (pintype "passive"))
      (node (ref "R4") (pin "2") (pinfunction "2_2") (pintype "passive"))
      (node (ref "U6") (pin "49") (pinfunction "IOB_47/SPI-SS-B_49") (pintype "bidirectional"))
    )
    (net (code "63") (name "/SPI_SS_E") (class "Default")
      (node (ref "J2") (pin "7") (pinfunction "7_7") (pintype "passive"))
      (node (ref "U6") (pin "37") (pinfunction "IOB_37_37") (pintype "bidirectional"))
    )
    (net (code "64") (name "/SRAM_CS") (class "Default")
      (node (ref "U6") (pin "78") (pinfunction "IOT_73_78") (pintype "bidirectional"))
      (node (ref "U7") (pin "6") (pinfunction "CS_6") (pintype "input"))
    )
    (net (code "65") (name "/SRAM_OE") (class "Default")
      (node (ref "U6") (pin "74") (pinfunction "IOR_72_74") (pintype "output"))
      (node (ref "U7") (pin "41") (pinfunction "OE_41") (pintype "input"))
    )
    (net (code "66") (name "/SRAM_WE") (class "Default")
      (node (ref "U6") (pin "73") (pinfunction "IOR_71_73") (pintype "bidirectional"))
      (node (ref "U7") (pin "17") (pinfunction "WE_17") (pintype "input"))
    )
    (net (code "67") (name "/SYSCLK") (class "Default")
      (node (ref "R13") (pin "1") (pinfunction "1_1") (pintype "passive"))
      (node (ref "U6") (pin "15") (pinfunction "IOL_7A/GBIN6_15") (pintype "bidirectional"))
    )
    (net (code "68") (name "/VPP_DIRECT_FAST") (class "Default")
      (node (ref "U6") (pin "76") (pinfunction "VPP_DIRECT_FAST_76") (pintype "power_in"))
    )
    (net (code "69") (name "15V") (class "Default")
      (node (ref "C12") (pin "2") (pinfunction "2_2") (pintype "passive"))
      (node (ref "J1") (pin "P$2") (pinfunction "VPOS_P$2") (pintype "bidirectional"))
      (node (ref "J1") (pin "P$4") (pinfunction "VPOS_P$4") (pintype "bidirectional"))
      (node (ref "RD4") (pin "1") (pinfunction "1_1") (pintype "passive"))
      (node (ref "U1") (pin "P$44") (pinfunction "VPOS_P$44") (pintype "bidirectional"))
    )
    (net (code "70") (name "22V") (class "Default")
      (node (ref "C11") (pin "1") (pinfunction "1_1") (pintype "passive"))
      (node (ref "D6") (pin "2") (pinfunction "C_2") (pintype "passive"))
      (node (ref "J1") (pin "P$25") (pinfunction "VGG_P$25") (pintype "bidirectional"))
      (node (ref "R9") (pin "2") (pinfunction "2_2") (pintype "passive"))
      (node (ref "RD2") (pin "1") (pinfunction "1_1") (pintype "passive"))
    )
    (net (code "71") (name "GND") (class "Default")
      (node (ref "C1") (pin "-") (pinfunction "-_-") (pintype "passive"))
      (node (ref "C10") (pin "2") (pinfunction "2_2") (pintype "passive"))
      (node (ref "C11") (pin "2") (pinfunction "2_2") (pintype "passive"))
      (node (ref "C12") (pin "1") (pinfunction "1_1") (pintype "passive"))
      (node (ref "C13") (pin "2") (pinfunction "2_2") (pintype "passive"))
      (node (ref "C14") (pin "1") (pinfunction "1_1") (pintype "passive"))
      (node (ref "C15") (pin "1") (pinfunction "1_1") (pintype "passive"))
      (node (ref "C16") (pin "1") (pinfunction "1_1") (pintype "passive"))
      (node (ref "C17") (pin "1") (pinfunction "1_1") (pintype "passive"))
      (node (ref "C18") (pin "1") (pinfunction "1_1") (pintype "passive"))
      (node (ref "C19") (pin "1") (pinfunction "1_1") (pintype "passive"))
      (node (ref "C2") (pin "-") (pinfunction "-_-") (pintype "passive"))
      (node (ref "C21") (pin "1") (pinfunction "1_1") (pintype "passive"))
      (node (ref "C22") (pin "1") (pinfunction "1_1") (pintype "passive"))
      (node (ref "C23") (pin "1") (pinfunction "1_1") (pintype "passive"))
      (node (ref "C24") (pin "1") (pinfunction "1_1") (pintype "passive"))
      (node (ref "C25") (pin "1") (pinfunction "1_1") (pintype "passive"))
      (node (ref "C26") (pin "1") (pinfunction "1_1") (pintype "passive"))
      (node (ref "C27") (pin "1") (pinfunction "1_1") (pintype "passive"))
      (node (ref "C28") (pin "1") (pinfunction "1_1") (pintype "passive"))
      (node (ref "C29") (pin "1") (pinfunction "1_1") (pintype "passive"))
      (node (ref "C3") (pin "-") (pinfunction "-_-") (pintype "passive"))
      (node (ref "C30") (pin "1") (pinfunction "1_1") (pintype "passive"))
      (node (ref "C31") (pin "1") (pinfunction "1_1") (pintype "passive"))
      (node (ref "C32") (pin "1") (pinfunction "1_1") (pintype "passive"))
      (node (ref "C33") (pin "1") (pinfunction "1_1") (pintype "passive"))
      (node (ref "C34") (pin "1") (pinfunction "1_1") (pintype "passive"))
      (node (ref "C35") (pin "1") (pinfunction "1_1") (pintype "passive"))
      (node (ref "C36") (pin "1") (pinfunction "1_1") (pintype "passive"))
      (node (ref "C37") (pin "1") (pinfunction "1_1") (pintype "passive"))
      (node (ref "C39") (pin "1") (pinfunction "1_1") (pintype "passive"))
      (node (ref "C4") (pin "-") (pinfunction "-_-") (pintype "passive"))
      (node (ref "C40") (pin "1") (pinfunction "1_1") (pintype "passive"))
      (node (ref "C41") (pin "1") (pinfunction "1_1") (pintype "passive"))
      (node (ref "C42") (pin "1") (pinfunction "1_1") (pintype "passive"))
      (node (ref "C43") (pin "1") (pinfunction "1_1") (pintype "passive"))
      (node (ref "C5") (pin "1") (pinfunction "1_1") (pintype "passive"))
      (node (ref "C6") (pin "2") (pinfunction "2_2") (pintype "passive"))
      (node (ref "C7") (pin "2") (pinfunction "2_2") (pintype "passive"))
      (node (ref "C8") (pin "2") (pinfunction "2_2") (pintype "passive"))
      (node (ref "J1") (pin "P$31") (pinfunction "VSS_P$31") (pintype "bidirectional"))
      (node (ref "J1") (pin "P$32") (pinfunction "VBORDER_P$32") (pintype "bidirectional"))
      (node (ref "J1") (pin "P$6") (pinfunction "VSS_P$6") (pintype "bidirectional"))
      (node (ref "J1") (pin "P$8") (pinfunction "VSS_P$8") (pintype "bidirectional"))
      (node (ref "J2") (pin "15") (pinfunction "15_15") (pintype "passive"))
      (node (ref "L1") (pin "1") (pinfunction "1_1") (pintype "passive"))
      (node (ref "OSC1") (pin "2") (pinfunction "GND_2") (pintype "power_in"))
      (node (ref "R10") (pin "2") (pinfunction "2_2") (pintype "passive"))
      (node (ref "R12") (pin "1") (pinfunction "1_1") (pintype "passive"))
      (node (ref "R23") (pin "1") (pinfunction "1_1") (pintype "passive"))
      (node (ref "R27") (pin "1") (pinfunction "1_1") (pintype "passive"))
      (node (ref "RD5") (pin "2") (pinfunction "2_2") (pintype "passive"))
      (node (ref "U1") (pin "P$32") (pinfunction "PGND2_P$32") (pintype "bidirectional"))
      (node (ref "U1") (pin "P$41") (pinfunction "PGND1_P$41") (pintype "bidirectional"))
      (node (ref "U1") (pin "P$48") (pinfunction "AGND2_P$48") (pintype "bidirectional"))
      (node (ref "U1") (pin "P$6") (pinfunction "DGND_P$6") (pintype "bidirectional"))
      (node (ref "U1") (pin "P$8") (pinfunction "AGND1_P$8") (pintype "bidirectional"))
      (node (ref "U2") (pin "2") (pinfunction "GND_2") (pintype "bidirectional"))
      (node (ref "U3") (pin "2") (pinfunction "GND_2") (pintype "bidirectional"))
      (node (ref "U5") (pin "4") (pinfunction "VSS_4") (pintype "bidirectional"))
      (node (ref "U6") (pin "17") (pinfunction "GND$1_17") (pintype "power_in"))
      (node (ref "U6") (pin "23") (pinfunction "GND$2_23") (pintype "power_in"))
      (node (ref "U6") (pin "32") (pinfunction "GND$3_32") (pintype "power_in"))
      (node (ref "U6") (pin "39") (pinfunction "GND$4_39") (pintype "power_in"))
      (node (ref "U6") (pin "47") (pinfunction "GND$5_47") (pintype "power_in"))
      (node (ref "U6") (pin "5") (pinfunction "GND$0_5") (pintype "power_in"))
      (node (ref "U6") (pin "55") (pinfunction "GND$6_55") (pintype "power_in"))
      (node (ref "U6") (pin "70") (pinfunction "GND$7_70") (pintype "bidirectional"))
      (node (ref "U6") (pin "84") (pinfunction "GND$8_84") (pintype "power_in"))
      (node (ref "U6") (pin "98") (pinfunction "GND$9_98") (pintype "power_in"))
      (node (ref "U7") (pin "12") (pinfunction "VSS_12") (pintype "bidirectional"))
      (node (ref "U7") (pin "34") (pinfunction "VSS_34") (pintype "bidirectional"))
      (node (ref "U7") (pin "39") (pinfunction "BLE_39") (pintype "input"))
      (node (ref "U7") (pin "40") (pinfunction "BHE_40") (pintype "input"))
    )
    (net (code "72") (name "Net-(D4-A)") (class "Default")
      (node (ref "D4") (pin "2") (pinfunction "A_2") (pintype "passive"))
      (node (ref "L3") (pin "1") (pinfunction "1_1") (pintype "passive"))
      (node (ref "U1") (pin "P$40") (pinfunction "VB_SW_P$40") (pintype "bidirectional"))
    )
    (net (code "73") (name "Net-(D4-C)") (class "Default")
      (node (ref "C7") (pin "1") (pinfunction "1_1") (pintype "passive"))
      (node (ref "C8") (pin "1") (pinfunction "1_1") (pintype "passive"))
      (node (ref "D4") (pin "1") (pinfunction "C_1") (pintype "passive"))
      (node (ref "U1") (pin "P$37") (pinfunction "VDDH_IN_P$37") (pintype "bidirectional"))
      (node (ref "U1") (pin "P$42") (pinfunction "VB_P$42") (pintype "bidirectional"))
      (node (ref "U1") (pin "P$43") (pinfunction "VPOS_IN_P$43") (pintype "bidirectional"))
    )
    (net (code "74") (name "Net-(D6-A)") (class "Default")
      (node (ref "C10") (pin "1") (pinfunction "1_1") (pintype "passive"))
      (node (ref "D6") (pin "1") (pinfunction "A_1") (pintype "passive"))
      (node (ref "U1") (pin "P$34") (pinfunction "VDDH_D_P$34") (pintype "bidirectional"))
    )
    (net (code "75") (name "Net-(D6-AC)") (class "Default")
      (node (ref "C9") (pin "2") (pinfunction "2_2") (pintype "passive"))
      (node (ref "D6") (pin "3") (pinfunction "AC_3") (pintype "passive"))
    )
    (net (code "76") (name "Net-(D7-A)") (class "Default")
      (node (ref "C15") (pin "2") (pinfunction "2_2") (pintype "passive"))
      (node (ref "C16") (pin "2") (pinfunction "2_2") (pintype "passive"))
      (node (ref "C17") (pin "2") (pinfunction "2_2") (pintype "passive"))
      (node (ref "D7") (pin "2") (pinfunction "A_2") (pintype "passive"))
      (node (ref "U1") (pin "EP") (pinfunction "POWERPAD_EP") (pintype "bidirectional"))
      (node (ref "U1") (pin "EP1") (pinfunction "POWERPAD_EP1") (pintype "bidirectional"))
      (node (ref "U1") (pin "EP10") (pinfunction "POWERPAD_EP10") (pintype "bidirectional"))
      (node (ref "U1") (pin "EP11") (pinfunction "POWERPAD_EP11") (pintype "bidirectional"))
      (node (ref "U1") (pin "EP12") (pinfunction "POWERPAD_EP12") (pintype "bidirectional"))
      (node (ref "U1") (pin "EP13") (pinfunction "POWERPAD_EP13") (pintype "bidirectional"))
      (node (ref "U1") (pin "EP14") (pinfunction "POWERPAD_EP14") (pintype "bidirectional"))
      (node (ref "U1") (pin "EP15") (pinfunction "POWERPAD_EP15") (pintype "bidirectional"))
      (node (ref "U1") (pin "EP16") (pinfunction "POWERPAD_EP16") (pintype "bidirectional"))
      (node (ref "U1") (pin "EP2") (pinfunction "POWERPAD_EP2") (pintype "bidirectional"))
      (node (ref "U1") (pin "EP3") (pinfunction "POWERPAD_EP3") (pintype "bidirectional"))
      (node (ref "U1") (pin "EP4") (pinfunction "POWERPAD_EP4") (pintype "bidirectional"))
      (node (ref "U1") (pin "EP5") (pinfunction "POWERPAD_EP5") (pintype "bidirectional"))
      (node (ref "U1") (pin "EP6") (pinfunction "POWERPAD_EP6") (pintype "bidirectional"))
      (node (ref "U1") (pin "EP7") (pinfunction "POWERPAD_EP7") (pintype "bidirectional"))
      (node (ref "U1") (pin "EP8") (pinfunction "POWERPAD_EP8") (pintype "bidirectional"))
      (node (ref "U1") (pin "EP9") (pinfunction "POWERPAD_EP9") (pintype "bidirectional"))
      (node (ref "U1") (pin "P$16") (pinfunction "VCOM_PWR_P$16") (pintype "bidirectional"))
      (node (ref "U1") (pin "P$22") (pinfunction "PBKG_P$22") (pintype "bidirectional"))
      (node (ref "U1") (pin "P$26") (pinfunction "VN_P$26") (pintype "bidirectional"))
      (node (ref "U1") (pin "P$27") (pinfunction "VEE_IN_P$27") (pintype "bidirectional"))
      (node (ref "U1") (pin "P$4") (pinfunction "VNEG_IN_P$4") (pintype "bidirectional"))
    )
    (net (code "77") (name "Net-(D7-C)") (class "Default")
      (node (ref "D7") (pin "1") (pinfunction "C_1") (pintype "passive"))
      (node (ref "L1") (pin "2") (pinfunction "2_2") (pintype "passive"))
      (node (ref "U1") (pin "P$25") (pinfunction "VN_SW_P$25") (pintype "bidirectional"))
    )
    (net (code "78") (name "Net-(D8-AC)") (class "Default")
      (node (ref "C20") (pin "2") (pinfunction "2_2") (pintype "passive"))
      (node (ref "D8") (pin "3") (pinfunction "AC_3") (pintype "passive"))
    )
    (net (code "79") (name "Net-(D8-C)") (class "Default")
      (node (ref "C21") (pin "2") (pinfunction "2_2") (pintype "passive"))
      (node (ref "D8") (pin "2") (pinfunction "C_2") (pintype "passive"))
      (node (ref "U1") (pin "P$30") (pinfunction "VEE_D_P$30") (pintype "bidirectional"))
    )
    (net (code "80") (name "Net-(OSC1-OUT)") (class "Default")
      (node (ref "OSC1") (pin "3") (pinfunction "OUT_3") (pintype "output"))
      (node (ref "R13") (pin "2") (pinfunction "2_2") (pintype "passive"))
    )
    (net (code "81") (name "Net-(U1-INT_LDO)") (class "Default")
      (node (ref "C18") (pin "2") (pinfunction "2_2") (pintype "passive"))
      (node (ref "U1") (pin "P$7") (pinfunction "INT_LDO_P$7") (pintype "bidirectional"))
    )
    (net (code "82") (name "Net-(U1-TS)") (class "Default")
      (node (ref "R23") (pin "2") (pinfunction "2_2") (pintype "passive"))
      (node (ref "R27") (pin "2") (pinfunction "2_2") (pintype "passive"))
      (node (ref "U1") (pin "P$47") (pinfunction "TS_P$47") (pintype "bidirectional"))
    )
    (net (code "83") (name "Net-(U1-VCOM_DIS)") (class "Default")
      (node (ref "RD5") (pin "1") (pinfunction "1_1") (pintype "passive"))
      (node (ref "U1") (pin "P$14") (pinfunction "VCOM_DIS_P$14") (pintype "bidirectional"))
    )
    (net (code "84") (name "Net-(U1-VDDH_DIS)") (class "Default")
      (node (ref "RD2") (pin "2") (pinfunction "2_2") (pintype "passive"))
      (node (ref "U1") (pin "P$35") (pinfunction "VDDH_DIS_P$35") (pintype "bidirectional"))
    )
    (net (code "85") (name "Net-(U1-VDDH_DRV)") (class "Default")
      (node (ref "C9") (pin "1") (pinfunction "1_1") (pintype "passive"))
      (node (ref "U1") (pin "P$36") (pinfunction "VDDH_DRV_P$36") (pintype "bidirectional"))
    )
    (net (code "86") (name "Net-(U1-VDDH_FB)") (class "Default")
      (node (ref "R10") (pin "1") (pinfunction "1_1") (pintype "passive"))
      (node (ref "R9") (pin "1") (pinfunction "1_1") (pintype "passive"))
      (node (ref "U1") (pin "P$33") (pinfunction "VDDH_FB_P$33") (pintype "bidirectional"))
    )
    (net (code "87") (name "Net-(U1-VEE_DIS)") (class "Default")
      (node (ref "RD1") (pin "1") (pinfunction "1_1") (pintype "passive"))
      (node (ref "U1") (pin "P$29") (pinfunction "VEE_DIS_P$29") (pintype "bidirectional"))
    )
    (net (code "88") (name "Net-(U1-VEE_DRV)") (class "Default")
      (node (ref "C20") (pin "1") (pinfunction "1_1") (pintype "passive"))
      (node (ref "U1") (pin "P$28") (pinfunction "VEE_DRV_P$28") (pintype "bidirectional"))
    )
    (net (code "89") (name "Net-(U1-VEE_FB)") (class "Default")
      (node (ref "R11") (pin "2") (pinfunction "2_2") (pintype "passive"))
      (node (ref "R12") (pin "2") (pinfunction "2_2") (pintype "passive"))
      (node (ref "U1") (pin "P$31") (pinfunction "VEE_FB_P$31") (pintype "bidirectional"))
    )
    (net (code "90") (name "Net-(U1-VNEG_DIS)") (class "Default")
      (node (ref "RD3") (pin "1") (pinfunction "1_1") (pintype "passive"))
      (node (ref "U1") (pin "P$9") (pinfunction "VNEG_DIS_P$9") (pintype "bidirectional"))
    )
    (net (code "91") (name "Net-(U1-VPOS_DIS)") (class "Default")
      (node (ref "RD4") (pin "2") (pinfunction "2_2") (pintype "passive"))
      (node (ref "U1") (pin "P$19") (pinfunction "VPOS_DIS_P$19") (pintype "bidirectional"))
    )
    (net (code "92") (name "Net-(U1-VREF)") (class "Default")
      (node (ref "C19") (pin "2") (pinfunction "2_2") (pintype "passive"))
      (node (ref "U1") (pin "P$1") (pinfunction "VREF_P$1") (pintype "bidirectional"))
    )
    (net (code "93") (name "Net-(U2-SW)") (class "Default")
      (node (ref "L2") (pin "1") (pinfunction "1_1") (pintype "passive"))
      (node (ref "U2") (pin "5") (pinfunction "SW_5") (pintype "bidirectional"))
    )
    (net (code "94") (name "Net-(U3-SW)") (class "Default")
      (node (ref "L4") (pin "1") (pinfunction "1_1") (pintype "passive"))
      (node (ref "U3") (pin "5") (pinfunction "SW_5") (pintype "bidirectional"))
    )
    (net (code "95") (name "Net-(U5-#HOLD{slash}IO3)") (class "Default")
      (node (ref "R3") (pin "1") (pinfunction "1_1") (pintype "passive"))
      (node (ref "U5") (pin "3") (pinfunction "#WP/IO2_3") (pintype "bidirectional"))
      (node (ref "U5") (pin "7") (pinfunction "#HOLD/IO3_7") (pintype "bidirectional"))
    )
    (net (code "96") (name "Net-(U5-SSEL)") (class "Default")
      (node (ref "R4") (pin "1") (pinfunction "1_1") (pintype "passive"))
      (node (ref "R5") (pin "2") (pinfunction "2_2") (pintype "passive"))
      (node (ref "U5") (pin "1") (pinfunction "SSEL_1") (pintype "bidirectional"))
    )
    (net (code "97") (name "Net-(U6-VPP_2V5_PUMP)") (class "Default")
      (node (ref "D1") (pin "C") (pinfunction "C_C") (pintype "passive"))
      (node (ref "U6") (pin "75") (pinfunction "VPP_2V5_PUMP_75") (pintype "power_in"))
    )
    (net (code "98") (name "SCL") (class "Default")
      (node (ref "J2") (pin "10") (pinfunction "10_10") (pintype "passive"))
      (node (ref "U1") (pin "P$17") (pinfunction "SCL_P$17") (pintype "bidirectional"))
    )
    (net (code "99") (name "SDA") (class "Default")
      (node (ref "J2") (pin "9") (pinfunction "9_9") (pintype "passive"))
      (node (ref "U1") (pin "P$18") (pinfunction "SDA_P$18") (pintype "bidirectional"))
    )
    (net (code "100") (name "VCC") (class "Default")
      (node (ref "C1") (pin "+") (pinfunction "+_+") (pintype "passive"))
      (node (ref "C13") (pin "1") (pinfunction "1_1") (pintype "passive"))
      (node (ref "C14") (pin "2") (pinfunction "2_2") (pintype "passive"))
      (node (ref "C3") (pin "+") (pinfunction "+_+") (pintype "passive"))
      (node (ref "C6") (pin "1") (pinfunction "1_1") (pintype "passive"))
      (node (ref "J2") (pin "16") (pinfunction "16_16") (pintype "passive"))
      (node (ref "L3") (pin "2") (pinfunction "2_2") (pintype "passive"))
      (node (ref "U1") (pin "P$10") (pinfunction "VIN_P$10") (pintype "bidirectional"))
      (node (ref "U1") (pin "P$24") (pinfunction "VIN_P_P$24") (pintype "bidirectional"))
      (node (ref "U2") (pin "1") (pinfunction "VIN_1") (pintype "bidirectional"))
      (node (ref "U3") (pin "1") (pinfunction "VIN_1") (pintype "bidirectional"))
    )
    (net (code "101") (name "VCOM") (class "Default")
      (node (ref "C24") (pin "2") (pinfunction "2_2") (pintype "passive"))
      (node (ref "J1") (pin "P$21") (pinfunction "VCOM_P$21") (pintype "bidirectional"))
      (node (ref "J1") (pin "P$23") (pinfunction "VCOM_P$23") (pintype "bidirectional"))
      (node (ref "U1") (pin "P$15") (pinfunction "VCOM_P$15") (pintype "bidirectional"))
    )
    (net (code "102") (name "WAKEUP") (class "Default")
      (node (ref "J2") (pin "11") (pinfunction "11_11") (pintype "passive"))
      (node (ref "U1") (pin "P$5") (pinfunction "WAKEUP_P$5") (pintype "bidirectional"))
    )
    (net (code "103") (name "unconnected-(J1-SPI_NCS-PadP$33)") (class "Default")
      (node (ref "J1") (pin "P$33") (pinfunction "SPI_NCS_P$33") (pintype "bidirectional"))
    )
    (net (code "104") (name "unconnected-(J1-SPI_SCL-PadP$22)") (class "Default")
      (node (ref "J1") (pin "P$22") (pinfunction "SPI_SCL_P$22") (pintype "bidirectional"))
    )
    (net (code "105") (name "unconnected-(J1-SPI_SDI-PadP$24)") (class "Default")
      (node (ref "J1") (pin "P$24") (pinfunction "SPI_SDI_P$24") (pintype "bidirectional"))
    )
    (net (code "106") (name "unconnected-(J1-SPI_SDO-PadP$34)") (class "Default")
      (node (ref "J1") (pin "P$34") (pinfunction "SPI_SDO_P$34") (pintype "bidirectional"))
    )
    (net (code "107") (name "unconnected-(U1-PWR_GOOD-PadP$23)") (class "Default")
      (node (ref "U1") (pin "P$23") (pinfunction "PWR_GOOD_P$23") (pintype "bidirectional"))
    )
    (net (code "108") (name "unconnected-(U1-V3P3-PadP$46)") (class "Default")
      (node (ref "U1") (pin "P$46") (pinfunction "V3P3_P$46") (pintype "bidirectional"))
    )
    (net (code "109") (name "unconnected-(U1-VIN3P3-PadP$45)") (class "Default")
      (node (ref "U1") (pin "P$45") (pinfunction "VIN3P3_P$45") (pintype "bidirectional"))
    )
    (net (code "110") (name "unconnected-(U6-IOB_26-Pad26)") (class "Default")
      (node (ref "U6") (pin "26") (pinfunction "IOB_26_26") (pintype "bidirectional"))
    )
    (net (code "111") (name "unconnected-(U6-IOB_27-Pad27)") (class "Default")
      (node (ref "U6") (pin "27") (pinfunction "IOB_27_27") (pintype "bidirectional"))
    )
    (net (code "112") (name "unconnected-(U6-IOB_28-Pad28)") (class "Default")
      (node (ref "U6") (pin "28") (pinfunction "IOB_28_28") (pintype "bidirectional"))
    )
    (net (code "113") (name "unconnected-(U6-IOB_29-Pad29)") (class "Default")
      (node (ref "U6") (pin "29") (pinfunction "IOB_29_29") (pintype "bidirectional"))
    )
    (net (code "114") (name "unconnected-(U6-IOB_30-Pad30)") (class "Default")
      (node (ref "U6") (pin "30") (pinfunction "IOB_30_30") (pintype "bidirectional"))
    )
    (net (code "115") (name "unconnected-(U6-IOB_34-Pad36)") (class "Default")
      (node (ref "U6") (pin "36") (pinfunction "IOB_34_36") (pintype "bidirectional"))
    )
    (net (code "116") (name "unconnected-(U6-IOB_35{slash}GBIN5-Pad33)") (class "Default")
      (node (ref "U6") (pin "33") (pinfunction "IOB_35/GBIN5_33") (pintype "bidirectional"))
    )
    (net (code "117") (name "unconnected-(U6-IOB_36{slash}GBIN4-Pad34)") (class "Default")
      (node (ref "U6") (pin "34") (pinfunction "IOB_36/GBIN4_34") (pintype "bidirectional"))
    )
    (net (code "118") (name "unconnected-(U6-IOB_41-Pad40)") (class "Default")
      (node (ref "U6") (pin "40") (pinfunction "IOB_41_40") (pintype "bidirectional"))
    )
    (net (code "119") (name "unconnected-(U6-IOB_42{slash}CBSEL0-Pad41)") (class "Default")
      (node (ref "U6") (pin "41") (pinfunction "IOB_42/CBSEL0_41") (pintype "bidirectional"))
    )
    (net (code "120") (name "unconnected-(U6-IOB_43{slash}CBSEL1-Pad42)") (class "Default")
      (node (ref "U6") (pin "42") (pinfunction "IOB_43/CBSEL1_42") (pintype "bidirectional"))
    )
    (net (code "121") (name "unconnected-(U6-IOL_6A-Pad12)") (class "Default")
      (node (ref "U6") (pin "12") (pinfunction "IOL_6A_12") (pintype "bidirectional"))
    )
    (net (code "122") (name "unconnected-(U6-IOL_6B{slash}GBIN7-Pad13)") (class "Default")
      (node (ref "U6") (pin "13") (pinfunction "IOL_6B/GBIN7_13") (pintype "bidirectional"))
    )
    (net (code "123") (name "unconnected-(U6-IOR_52-Pad51)") (class "Default")
      (node (ref "U6") (pin "51") (pinfunction "IOR_52_51") (pintype "bidirectional"))
    )
  )
)
